# FSAE_CONTROLLER_DEUTSCH.net
KiCad netlist of a schematic drawn in EAGLE
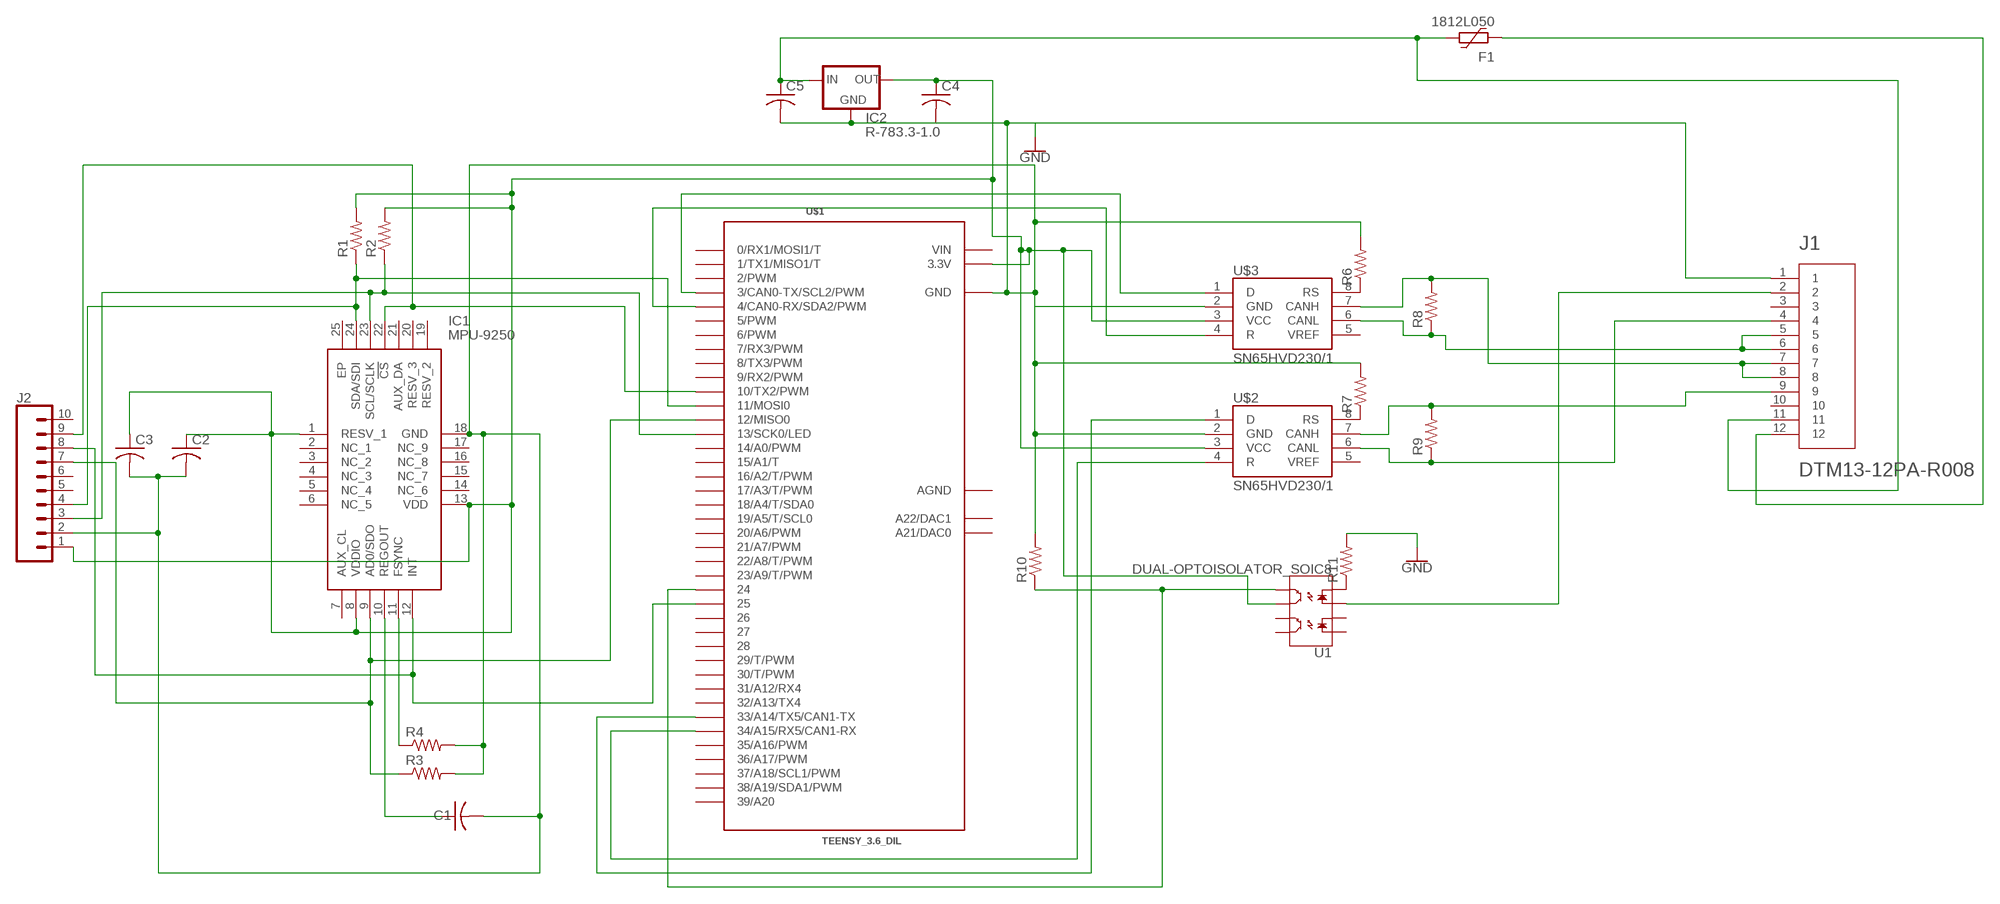
[diagram p0: schematic, sheet 1]

(export (version "E")
  (design (tool "Eeschema 10.0.6"))
  (components
    (comp (ref "C1")
      (value "C-USC1206")
      (footprint "eagle-import:C1206")
      (libsource (lib "eagle-import") (part "C-USC1206"))
    )
    (comp (ref "C2")
      (value "C-USC1206")
      (footprint "eagle-import:C1206")
      (libsource (lib "eagle-import") (part "C-USC1206"))
    )
    (comp (ref "C3")
      (value "C-USC1206")
      (footprint "eagle-import:C1206")
      (libsource (lib "eagle-import") (part "C-USC1206"))
    )
    (comp (ref "C4")
      (value "C-USC1206")
      (footprint "eagle-import:C1206")
      (libsource (lib "eagle-import") (part "C-USC1206"))
    )
    (comp (ref "C5")
      (value "C-USC1206")
      (footprint "eagle-import:C1206")
      (libsource (lib "eagle-import") (part "C-USC1206"))
    )
    (comp (ref "F1")
      (value "1812L050")
      (footprint "eagle-import:1812L")
      (fields (field (name "MF") "Littelfuse"))
      (libsource (lib "eagle-import") (part "?1812L050"))
    )
    (comp (ref "IC1")
      (value "MPU-9250")
      (footprint "eagle-import:QFN40P300X300X105-25N")
      (fields (field (name "MOUSER_PART_NUMBER") "410-MPU-9250") (field (name "RS_PART_NUMBER") "1774858"))
      (libsource (lib "eagle-import") (part "MPU-9250"))
    )
    (comp (ref "IC2")
      (value "R-783.3-1.0")
      (footprint "eagle-import:SIP3")
      (fields (field (name "MF") "Recom"))
      (libsource (lib "eagle-import") (part "R-78-1.03.3"))
    )
    (comp (ref "J1")
      (value "DTM13-12PA-R008")
      (footprint "eagle-import:TE_DTM13-12PA-R008")
      (fields (field (name "MF") "TE Connectivity") (field (name "MP") "DTM13-12PA-R008 "))
      (libsource (lib "eagle-import") (part "DTM13-12PA-R008"))
    )
    (comp (ref "J2")
      (value "CONN_10\"")
      (footprint "eagle-import:1X10")
      (libsource (lib "eagle-import") (part "CONN_10{dblquote}"))
    )
    (comp (ref "R1")
      (value "R-US_R1206")
      (footprint "eagle-import:R1206")
      (libsource (lib "eagle-import") (part "R-US_R1206"))
    )
    (comp (ref "R2")
      (value "R-US_R1206")
      (footprint "eagle-import:R1206")
      (libsource (lib "eagle-import") (part "R-US_R1206"))
    )
    (comp (ref "R3")
      (value "R-US_R1206")
      (footprint "eagle-import:R1206")
      (libsource (lib "eagle-import") (part "R-US_R1206"))
    )
    (comp (ref "R4")
      (value "R-US_R1206")
      (footprint "eagle-import:R1206")
      (libsource (lib "eagle-import") (part "R-US_R1206"))
    )
    (comp (ref "R6")
      (value "R-US_R1206")
      (footprint "eagle-import:R1206")
      (libsource (lib "eagle-import") (part "R-US_R1206"))
    )
    (comp (ref "R7")
      (value "R-US_R1206")
      (footprint "eagle-import:R1206")
      (libsource (lib "eagle-import") (part "R-US_R1206"))
    )
    (comp (ref "R8")
      (value "R-US_R1206")
      (footprint "eagle-import:R1206")
      (libsource (lib "eagle-import") (part "R-US_R1206"))
    )
    (comp (ref "R9")
      (value "R-US_R1206")
      (footprint "eagle-import:R1206")
      (libsource (lib "eagle-import") (part "R-US_R1206"))
    )
    (comp (ref "R10")
      (value "R-US_R1206")
      (footprint "eagle-import:R1206")
      (libsource (lib "eagle-import") (part "R-US_R1206"))
    )
    (comp (ref "R11")
      (value "R-US_R1206")
      (footprint "eagle-import:R1206")
      (libsource (lib "eagle-import") (part "R-US_R1206"))
    )
    (comp (ref "U$1")
      (value "TEENSY_3.6_DIL")
      (footprint "eagle-import:TEENSY_3.6_DIL")
      (libsource (lib "eagle-import") (part "TEENSY_3.6_DIL"))
    )
    (comp (ref "U$2")
      (value "SN65HVD230/1")
      (footprint "eagle-import:SO8")
      (libsource (lib "eagle-import") (part "SN65HVD230/1"))
    )
    (comp (ref "U$3")
      (value "SN65HVD230/1")
      (footprint "eagle-import:SO8")
      (libsource (lib "eagle-import") (part "SN65HVD230/1"))
    )
    (comp (ref "U1")
      (value "DUAL-OPTOISOLATOR_SOIC8")
      (footprint "eagle-import:SO08")
      (libsource (lib "eagle-import") (part "DUAL-OPTOISOLATOR_SOIC8"))
    )
  )
  (nets
    (net (code "1") (name "/AGND") (class "Default")
      (node (ref "U$1") (pin "AGND") (pinfunction "AGND_AGND") (pintype "power_in"))
    )
    (net (code "2") (name "/VIN") (class "Default")
      (node (ref "U$1") (pin "VIN") (pinfunction "VIN_VIN") (pintype "power_in"))
    )
    (net (code "3") (name "GND") (class "Default")
      (node (ref "C1") (pin "2") (pinfunction "2_2") (pintype "passive"))
      (node (ref "C2") (pin "2") (pinfunction "2_2") (pintype "passive"))
      (node (ref "C3") (pin "2") (pinfunction "2_2") (pintype "passive"))
      (node (ref "C4") (pin "2") (pinfunction "2_2") (pintype "passive"))
      (node (ref "C5") (pin "2") (pinfunction "2_2") (pintype "passive"))
      (node (ref "IC1") (pin "18") (pinfunction "GND_18") (pintype "bidirectional"))
      (node (ref "IC2") (pin "2") (pinfunction "GND_2") (pintype "input"))
      (node (ref "J1") (pin "1") (pinfunction "1_1") (pintype "passive"))
      (node (ref "J2") (pin "2") (pinfunction "2_2") (pintype "passive"))
      (node (ref "R10") (pin "2") (pinfunction "2_2") (pintype "passive"))
      (node (ref "R11") (pin "2") (pinfunction "2_2") (pintype "passive"))
      (node (ref "R3") (pin "2") (pinfunction "2_2") (pintype "passive"))
      (node (ref "R4") (pin "2") (pinfunction "2_2") (pintype "passive"))
      (node (ref "R6") (pin "2") (pinfunction "2_2") (pintype "passive"))
      (node (ref "R7") (pin "2") (pinfunction "2_2") (pintype "passive"))
      (node (ref "U$1") (pin "GND") (pinfunction "GND_GND") (pintype "power_in"))
      (node (ref "U$1") (pin "GND1") (pinfunction "GND_GND1") (pintype "power_in"))
      (node (ref "U$2") (pin "2") (pinfunction "GND_2") (pintype "power_in"))
      (node (ref "U$3") (pin "2") (pinfunction "GND_2") (pintype "power_in"))
    )
    (net (code "4") (name "Net-(F1-Pad2)") (class "Default")
      (node (ref "F1") (pin "2") (pinfunction "2_2") (pintype "passive"))
      (node (ref "J1") (pin "12") (pinfunction "12_12") (pintype "passive"))
    )
    (net (code "5") (name "Net-(IC1-AD0{slash}SDO)") (class "Default")
      (node (ref "IC1") (pin "9") (pinfunction "AD0/SDO_9") (pintype "bidirectional"))
      (node (ref "J2") (pin "7") (pinfunction "7_7") (pintype "passive"))
      (node (ref "R3") (pin "1") (pinfunction "1_1") (pintype "passive"))
      (node (ref "U$1") (pin "12") (pinfunction "12/MISO0_12") (pintype "bidirectional"))
    )
    (net (code "6") (name "Net-(IC1-FSYNC)") (class "Default")
      (node (ref "IC1") (pin "11") (pinfunction "FSYNC_11") (pintype "bidirectional"))
      (node (ref "R4") (pin "1") (pinfunction "1_1") (pintype "passive"))
    )
    (net (code "7") (name "Net-(IC1-INT)") (class "Default")
      (node (ref "IC1") (pin "12") (pinfunction "INT_12") (pintype "bidirectional"))
      (node (ref "J2") (pin "8") (pinfunction "8_8") (pintype "passive"))
      (node (ref "U$1") (pin "25") (pinfunction "25_25") (pintype "bidirectional"))
    )
    (net (code "8") (name "Net-(IC1-REGOUT)") (class "Default")
      (node (ref "C1") (pin "1") (pinfunction "1_1") (pintype "passive"))
      (node (ref "IC1") (pin "10") (pinfunction "REGOUT_10") (pintype "bidirectional"))
    )
    (net (code "9") (name "Net-(IC1-RESV_1)") (class "Default")
      (node (ref "C2") (pin "1") (pinfunction "1_1") (pintype "passive"))
      (node (ref "C3") (pin "1") (pinfunction "1_1") (pintype "passive"))
      (node (ref "C4") (pin "1") (pinfunction "1_1") (pintype "passive"))
      (node (ref "IC1") (pin "1") (pinfunction "RESV_1_1") (pintype "bidirectional"))
      (node (ref "IC1") (pin "13") (pinfunction "VDD_13") (pintype "bidirectional"))
      (node (ref "IC1") (pin "8") (pinfunction "VDDIO_8") (pintype "bidirectional"))
      (node (ref "IC2") (pin "3") (pinfunction "OUT_3") (pintype "passive"))
      (node (ref "J2") (pin "1") (pinfunction "1_1") (pintype "passive"))
      (node (ref "R1") (pin "2") (pinfunction "2_2") (pintype "passive"))
      (node (ref "R2") (pin "2") (pinfunction "2_2") (pintype "passive"))
      (node (ref "U$1") (pin "3.3V") (pinfunction "3.3V_3.3V") (pintype "power_in"))
      (node (ref "U$1") (pin "3.3V3") (pinfunction "3.3V_3.3V3") (pintype "power_in"))
      (node (ref "U$2") (pin "3") (pinfunction "VCC_3") (pintype "power_in"))
      (node (ref "U$3") (pin "3") (pinfunction "VCC_3") (pintype "power_in"))
      (node (ref "U1") (pin "6") (pinfunction "CL2_6") (pintype "bidirectional"))
    )
    (net (code "10") (name "Net-(IC1-SCL{slash}SCLK)") (class "Default")
      (node (ref "IC1") (pin "23") (pinfunction "SCL/SCLK_23") (pintype "bidirectional"))
      (node (ref "J2") (pin "3") (pinfunction "3_3") (pintype "passive"))
      (node (ref "R2") (pin "1") (pinfunction "1_1") (pintype "passive"))
      (node (ref "U$1") (pin "13") (pinfunction "13/SCK0/LED_13") (pintype "bidirectional"))
    )
    (net (code "11") (name "Net-(IC1-SDA{slash}SDI)") (class "Default")
      (node (ref "IC1") (pin "24") (pinfunction "SDA/SDI_24") (pintype "bidirectional"))
      (node (ref "J2") (pin "4") (pinfunction "4_4") (pintype "passive"))
      (node (ref "R1") (pin "1") (pinfunction "1_1") (pintype "passive"))
      (node (ref "U$1") (pin "11") (pinfunction "11/MOSI0_11") (pintype "bidirectional"))
    )
    (net (code "12") (name "Net-(IC1-~{CS})") (class "Default")
      (node (ref "IC1") (pin "22") (pinfunction "~{CS}_22") (pintype "bidirectional"))
      (node (ref "J2") (pin "9") (pinfunction "9_9") (pintype "passive"))
      (node (ref "U$1") (pin "10") (pinfunction "10/TX2/PWM_10") (pintype "bidirectional"))
    )
    (net (code "13") (name "Net-(IC2-IN)") (class "Default")
      (node (ref "C5") (pin "1") (pinfunction "1_1") (pintype "passive"))
      (node (ref "F1") (pin "1") (pinfunction "1_1") (pintype "passive"))
      (node (ref "IC2") (pin "1") (pinfunction "IN_1") (pintype "input"))
      (node (ref "J1") (pin "11") (pinfunction "11_11") (pintype "passive"))
    )
    (net (code "14") (name "Net-(U$1-3{slash}CAN0-TX{slash}SCL2{slash}PWM)") (class "Default")
      (node (ref "U$1") (pin "3") (pinfunction "3/CAN0-TX/SCL2/PWM_3") (pintype "bidirectional"))
      (node (ref "U$3") (pin "1") (pinfunction "D_1") (pintype "bidirectional"))
    )
    (net (code "15") (name "Net-(U$1-4{slash}CAN0-RX{slash}SDA2{slash}PWM)") (class "Default")
      (node (ref "U$1") (pin "4") (pinfunction "4/CAN0-RX/SDA2/PWM_4") (pintype "bidirectional"))
      (node (ref "U$3") (pin "4") (pinfunction "R_4") (pintype "bidirectional"))
    )
    (net (code "16") (name "Net-(U$1-33{slash}A14{slash}TX5{slash}CAN1-TX)") (class "Default")
      (node (ref "U$1") (pin "33/A14") (pinfunction "33/A14/TX5/CAN1-TX_33/A14") (pintype "bidirectional"))
      (node (ref "U$2") (pin "1") (pinfunction "D_1") (pintype "bidirectional"))
    )
    (net (code "17") (name "Net-(U$1-34{slash}A15{slash}RX5{slash}CAN1-RX)") (class "Default")
      (node (ref "U$1") (pin "34/A15") (pinfunction "34/A15/RX5/CAN1-RX_34/A15") (pintype "bidirectional"))
      (node (ref "U$2") (pin "4") (pinfunction "R_4") (pintype "bidirectional"))
    )
    (net (code "18") (name "Net-(U$2-CANH)") (class "Default")
      (node (ref "J1") (pin "9") (pinfunction "9_9") (pintype "passive"))
      (node (ref "R9") (pin "2") (pinfunction "2_2") (pintype "passive"))
      (node (ref "U$2") (pin "7") (pinfunction "CANH_7") (pintype "bidirectional"))
    )
    (net (code "19") (name "Net-(U$2-CANL)") (class "Default")
      (node (ref "J1") (pin "4") (pinfunction "4_4") (pintype "passive"))
      (node (ref "R9") (pin "1") (pinfunction "1_1") (pintype "passive"))
      (node (ref "U$2") (pin "6") (pinfunction "CANL_6") (pintype "bidirectional"))
    )
    (net (code "20") (name "Net-(U$2-RS)") (class "Default")
      (node (ref "R7") (pin "1") (pinfunction "1_1") (pintype "passive"))
      (node (ref "U$2") (pin "8") (pinfunction "RS_8") (pintype "bidirectional"))
    )
    (net (code "21") (name "Net-(U$3-CANH)") (class "Default")
      (node (ref "J1") (pin "7") (pinfunction "7_7") (pintype "passive"))
      (node (ref "J1") (pin "8") (pinfunction "8_8") (pintype "passive"))
      (node (ref "R8") (pin "2") (pinfunction "2_2") (pintype "passive"))
      (node (ref "U$3") (pin "7") (pinfunction "CANH_7") (pintype "bidirectional"))
    )
    (net (code "22") (name "Net-(U$3-CANL)") (class "Default")
      (node (ref "J1") (pin "5") (pinfunction "5_5") (pintype "passive"))
      (node (ref "J1") (pin "6") (pinfunction "6_6") (pintype "passive"))
      (node (ref "R8") (pin "1") (pinfunction "1_1") (pintype "passive"))
      (node (ref "U$3") (pin "6") (pinfunction "CANL_6") (pintype "bidirectional"))
    )
    (net (code "23") (name "Net-(U$3-RS)") (class "Default")
      (node (ref "R6") (pin "1") (pinfunction "1_1") (pintype "passive"))
      (node (ref "U$3") (pin "8") (pinfunction "RS_8") (pintype "bidirectional"))
    )
    (net (code "24") (name "Net-(U1-A2)") (class "Default")
      (node (ref "J1") (pin "2") (pinfunction "2_2") (pintype "passive"))
      (node (ref "U1") (pin "3") (pinfunction "A2_3") (pintype "bidirectional"))
    )
    (net (code "25") (name "Net-(U1-C2)") (class "Default")
      (node (ref "R11") (pin "1") (pinfunction "1_1") (pintype "passive"))
      (node (ref "U1") (pin "4") (pinfunction "C2_4") (pintype "bidirectional"))
    )
    (net (code "26") (name "Net-(U1-EM2)") (class "Default")
      (node (ref "R10") (pin "1") (pinfunction "1_1") (pintype "passive"))
      (node (ref "U$1") (pin "24") (pinfunction "24_24") (pintype "bidirectional"))
      (node (ref "U1") (pin "5") (pinfunction "EM2_5") (pintype "bidirectional"))
    )
    (net (code "27") (name "unconnected-(IC1-AUX_CL-Pad7)") (class "Default")
      (node (ref "IC1") (pin "7") (pinfunction "AUX_CL_7") (pintype "bidirectional"))
    )
    (net (code "28") (name "unconnected-(IC1-AUX_DA-Pad21)") (class "Default")
      (node (ref "IC1") (pin "21") (pinfunction "AUX_DA_21") (pintype "bidirectional"))
    )
    (net (code "29") (name "unconnected-(IC1-EP-Pad25)") (class "Default")
      (node (ref "IC1") (pin "25") (pinfunction "EP_25") (pintype "bidirectional"))
    )
    (net (code "30") (name "unconnected-(IC1-NC_1-Pad2)") (class "Default")
      (node (ref "IC1") (pin "2") (pinfunction "NC_1_2") (pintype "bidirectional"))
    )
    (net (code "31") (name "unconnected-(IC1-NC_2-Pad3)") (class "Default")
      (node (ref "IC1") (pin "3") (pinfunction "NC_2_3") (pintype "bidirectional"))
    )
    (net (code "32") (name "unconnected-(IC1-NC_3-Pad4)") (class "Default")
      (node (ref "IC1") (pin "4") (pinfunction "NC_3_4") (pintype "bidirectional"))
    )
    (net (code "33") (name "unconnected-(IC1-NC_4-Pad5)") (class "Default")
      (node (ref "IC1") (pin "5") (pinfunction "NC_4_5") (pintype "bidirectional"))
    )
    (net (code "34") (name "unconnected-(IC1-NC_5-Pad6)") (class "Default")
      (node (ref "IC1") (pin "6") (pinfunction "NC_5_6") (pintype "bidirectional"))
    )
    (net (code "35") (name "unconnected-(IC1-NC_6-Pad14)") (class "Default")
      (node (ref "IC1") (pin "14") (pinfunction "NC_6_14") (pintype "bidirectional"))
    )
    (net (code "36") (name "unconnected-(IC1-NC_7-Pad15)") (class "Default")
      (node (ref "IC1") (pin "15") (pinfunction "NC_7_15") (pintype "bidirectional"))
    )
    (net (code "37") (name "unconnected-(IC1-NC_8-Pad16)") (class "Default")
      (node (ref "IC1") (pin "16") (pinfunction "NC_8_16") (pintype "bidirectional"))
    )
    (net (code "38") (name "unconnected-(IC1-NC_9-Pad17)") (class "Default")
      (node (ref "IC1") (pin "17") (pinfunction "NC_9_17") (pintype "bidirectional"))
    )
    (net (code "39") (name "unconnected-(IC1-RESV_2-Pad19)") (class "Default")
      (node (ref "IC1") (pin "19") (pinfunction "RESV_2_19") (pintype "bidirectional"))
    )
    (net (code "40") (name "unconnected-(IC1-RESV_3-Pad20)") (class "Default")
      (node (ref "IC1") (pin "20") (pinfunction "RESV_3_20") (pintype "bidirectional"))
    )
    (net (code "41") (name "unconnected-(J1-Pad3)") (class "Default")
      (node (ref "J1") (pin "3") (pinfunction "3_3") (pintype "passive"))
    )
    (net (code "42") (name "unconnected-(J1-Pad10)") (class "Default")
      (node (ref "J1") (pin "10") (pinfunction "10_10") (pintype "passive"))
    )
    (net (code "43") (name "unconnected-(J2-Pad5)") (class "Default")
      (node (ref "J2") (pin "5") (pinfunction "5_5") (pintype "passive"))
    )
    (net (code "44") (name "unconnected-(J2-Pad6)") (class "Default")
      (node (ref "J2") (pin "6") (pinfunction "6_6") (pintype "passive"))
    )
    (net (code "45") (name "unconnected-(J2-Pad10)") (class "Default")
      (node (ref "J2") (pin "10") (pinfunction "10_10") (pintype "passive"))
    )
    (net (code "46") (name "unconnected-(U$1-0{slash}RX1{slash}MOSI1{slash}T-Pad0)") (class "Default")
      (node (ref "U$1") (pin "0") (pinfunction "0/RX1/MOSI1/T_0") (pintype "bidirectional"))
    )
    (net (code "47") (name "unconnected-(U$1-1{slash}TX1{slash}MISO1{slash}T-Pad1)") (class "Default")
      (node (ref "U$1") (pin "1") (pinfunction "1/TX1/MISO1/T_1") (pintype "bidirectional"))
    )
    (net (code "48") (name "unconnected-(U$1-2{slash}PWM-Pad2)") (class "Default")
      (node (ref "U$1") (pin "2") (pinfunction "2/PWM_2") (pintype "bidirectional"))
    )
    (net (code "49") (name "unconnected-(U$1-5{slash}PWM-Pad5)") (class "Default")
      (node (ref "U$1") (pin "5") (pinfunction "5/PWM_5") (pintype "bidirectional"))
    )
    (net (code "50") (name "unconnected-(U$1-6{slash}PWM-Pad6)") (class "Default")
      (node (ref "U$1") (pin "6") (pinfunction "6/PWM_6") (pintype "bidirectional"))
    )
    (net (code "51") (name "unconnected-(U$1-7{slash}RX3{slash}PWM-Pad7)") (class "Default")
      (node (ref "U$1") (pin "7") (pinfunction "7/RX3/PWM_7") (pintype "bidirectional"))
    )
    (net (code "52") (name "unconnected-(U$1-8{slash}TX3{slash}PWM-Pad8)") (class "Default")
      (node (ref "U$1") (pin "8") (pinfunction "8/TX3/PWM_8") (pintype "bidirectional"))
    )
    (net (code "53") (name "unconnected-(U$1-9{slash}RX2{slash}PWM-Pad9)") (class "Default")
      (node (ref "U$1") (pin "9") (pinfunction "9/RX2/PWM_9") (pintype "bidirectional"))
    )
    (net (code "54") (name "unconnected-(U$1-14{slash}A0{slash}PWM-Pad14{slash}A0)") (class "Default")
      (node (ref "U$1") (pin "14/A0") (pinfunction "14/A0/PWM_14/A0") (pintype "bidirectional"))
    )
    (net (code "55") (name "unconnected-(U$1-15{slash}A1{slash}T-Pad15{slash}A1)") (class "Default")
      (node (ref "U$1") (pin "15/A1") (pinfunction "15/A1/T_15/A1") (pintype "bidirectional"))
    )
    (net (code "56") (name "unconnected-(U$1-16{slash}A2{slash}T{slash}PWM-Pad16{slash}A2)") (class "Default")
      (node (ref "U$1") (pin "16/A2") (pinfunction "16/A2/T/PWM_16/A2") (pintype "bidirectional"))
    )
    (net (code "57") (name "unconnected-(U$1-17{slash}A3{slash}T{slash}PWM-Pad17{slash}A3)") (class "Default")
      (node (ref "U$1") (pin "17/A3") (pinfunction "17/A3/T/PWM_17/A3") (pintype "bidirectional"))
    )
    (net (code "58") (name "unconnected-(U$1-18{slash}A4{slash}T{slash}SDA0-Pad18{slash}A4)") (class "Default")
      (node (ref "U$1") (pin "18/A4") (pinfunction "18/A4/T/SDA0_18/A4") (pintype "bidirectional"))
    )
    (net (code "59") (name "unconnected-(U$1-19{slash}A5{slash}T{slash}SCL0-Pad19{slash}A5)") (class "Default")
      (node (ref "U$1") (pin "19/A5") (pinfunction "19/A5/T/SCL0_19/A5") (pintype "bidirectional"))
    )
    (net (code "60") (name "unconnected-(U$1-20{slash}A6{slash}PWM-Pad20{slash}A6)") (class "Default")
      (node (ref "U$1") (pin "20/A6") (pinfunction "20/A6/PWM_20/A6") (pintype "bidirectional"))
    )
    (net (code "61") (name "unconnected-(U$1-21{slash}A7{slash}PWM-Pad21{slash}A7)") (class "Default")
      (node (ref "U$1") (pin "21/A7") (pinfunction "21/A7/PWM_21/A7") (pintype "bidirectional"))
    )
    (net (code "62") (name "unconnected-(U$1-22{slash}A8{slash}T{slash}PWM-Pad22{slash}A8)") (class "Default")
      (node (ref "U$1") (pin "22/A8") (pinfunction "22/A8/T/PWM_22/A8") (pintype "bidirectional"))
    )
    (net (code "63") (name "unconnected-(U$1-23{slash}A9{slash}T{slash}PWM-Pad23{slash}A9)") (class "Default")
      (node (ref "U$1") (pin "23/A9") (pinfunction "23/A9/T/PWM_23/A9") (pintype "bidirectional"))
    )
    (net (code "64") (name "unconnected-(U$1-29{slash}T{slash}PWM-Pad29)") (class "Default")
      (node (ref "U$1") (pin "29") (pinfunction "29/T/PWM_29") (pintype "bidirectional"))
    )
    (net (code "65") (name "unconnected-(U$1-30{slash}T{slash}PWM-Pad30)") (class "Default")
      (node (ref "U$1") (pin "30") (pinfunction "30/T/PWM_30") (pintype "bidirectional"))
    )
    (net (code "66") (name "unconnected-(U$1-31{slash}A12{slash}RX4-Pad31{slash}A12)") (class "Default")
      (node (ref "U$1") (pin "31/A12") (pinfunction "31/A12/RX4_31/A12") (pintype "bidirectional"))
    )
    (net (code "67") (name "unconnected-(U$1-32{slash}A13{slash}TX4-Pad32{slash}A13)") (class "Default")
      (node (ref "U$1") (pin "32/A13") (pinfunction "32/A13/TX4_32/A13") (pintype "bidirectional"))
    )
    (net (code "68") (name "unconnected-(U$1-35{slash}A16{slash}PWM-Pad35{slash}A16)") (class "Default")
      (node (ref "U$1") (pin "35/A16") (pinfunction "35/A16/PWM_35/A16") (pintype "bidirectional"))
    )
    (net (code "69") (name "unconnected-(U$1-36{slash}A17{slash}PWM-Pad36{slash}A17)") (class "Default")
      (node (ref "U$1") (pin "36/A17") (pinfunction "36/A17/PWM_36/A17") (pintype "bidirectional"))
    )
    (net (code "70") (name "unconnected-(U$1-37{slash}A18{slash}SCL1{slash}PWM-Pad37{slash}A18)") (class "Default")
      (node (ref "U$1") (pin "37/A18") (pinfunction "37/A18/SCL1/PWM_37/A18") (pintype "bidirectional"))
    )
    (net (code "71") (name "unconnected-(U$1-38{slash}A19{slash}SDA1{slash}PWM-Pad38{slash}A19)") (class "Default")
      (node (ref "U$1") (pin "38/A19") (pinfunction "38/A19/SDA1/PWM_38/A19") (pintype "bidirectional"))
    )
    (net (code "72") (name "unconnected-(U$1-A21{slash}DAC0-PadA21)") (class "Default")
      (node (ref "U$1") (pin "A21") (pinfunction "A21/DAC0_A21") (pintype "bidirectional"))
    )
    (net (code "73") (name "unconnected-(U$1-A22{slash}DAC1-PadA22)") (class "Default")
      (node (ref "U$1") (pin "A22") (pinfunction "A22/DAC1_A22") (pintype "bidirectional"))
    )
    (net (code "74") (name "unconnected-(U$1-Pad26)") (class "Default")
      (node (ref "U$1") (pin "26") (pinfunction "26_26") (pintype "bidirectional"))
    )
    (net (code "75") (name "unconnected-(U$1-Pad27)") (class "Default")
      (node (ref "U$1") (pin "27") (pinfunction "27_27") (pintype "bidirectional"))
    )
    (net (code "76") (name "unconnected-(U$1-Pad28)") (class "Default")
      (node (ref "U$1") (pin "28") (pinfunction "28_28") (pintype "bidirectional"))
    )
    (net (code "77") (name "unconnected-(U$1-Pad39{slash}A20)") (class "Default")
      (node (ref "U$1") (pin "39/A20") (pinfunction "39/A20_39/A20") (pintype "bidirectional"))
    )
    (net (code "78") (name "unconnected-(U$2-VREF-Pad5)") (class "Default")
      (node (ref "U$2") (pin "5") (pinfunction "VREF_5") (pintype "bidirectional"))
    )
    (net (code "79") (name "unconnected-(U$3-VREF-Pad5)") (class "Default")
      (node (ref "U$3") (pin "5") (pinfunction "VREF_5") (pintype "bidirectional"))
    )
    (net (code "80") (name "unconnected-(U1-A1-Pad1)") (class "Default")
      (node (ref "U1") (pin "1") (pinfunction "A1_1") (pintype "bidirectional"))
    )
    (net (code "81") (name "unconnected-(U1-C1-Pad2)") (class "Default")
      (node (ref "U1") (pin "2") (pinfunction "C1_2") (pintype "bidirectional"))
    )
    (net (code "82") (name "unconnected-(U1-CL1-Pad8)") (class "Default")
      (node (ref "U1") (pin "8") (pinfunction "CL1_8") (pintype "bidirectional"))
    )
    (net (code "83") (name "unconnected-(U1-EM1-Pad7)") (class "Default")
      (node (ref "U1") (pin "7") (pinfunction "EM1_7") (pintype "bidirectional"))
    )
  )
)
